# cpx-wroom32d.net
KiCad netlist of a schematic drawn in EAGLE
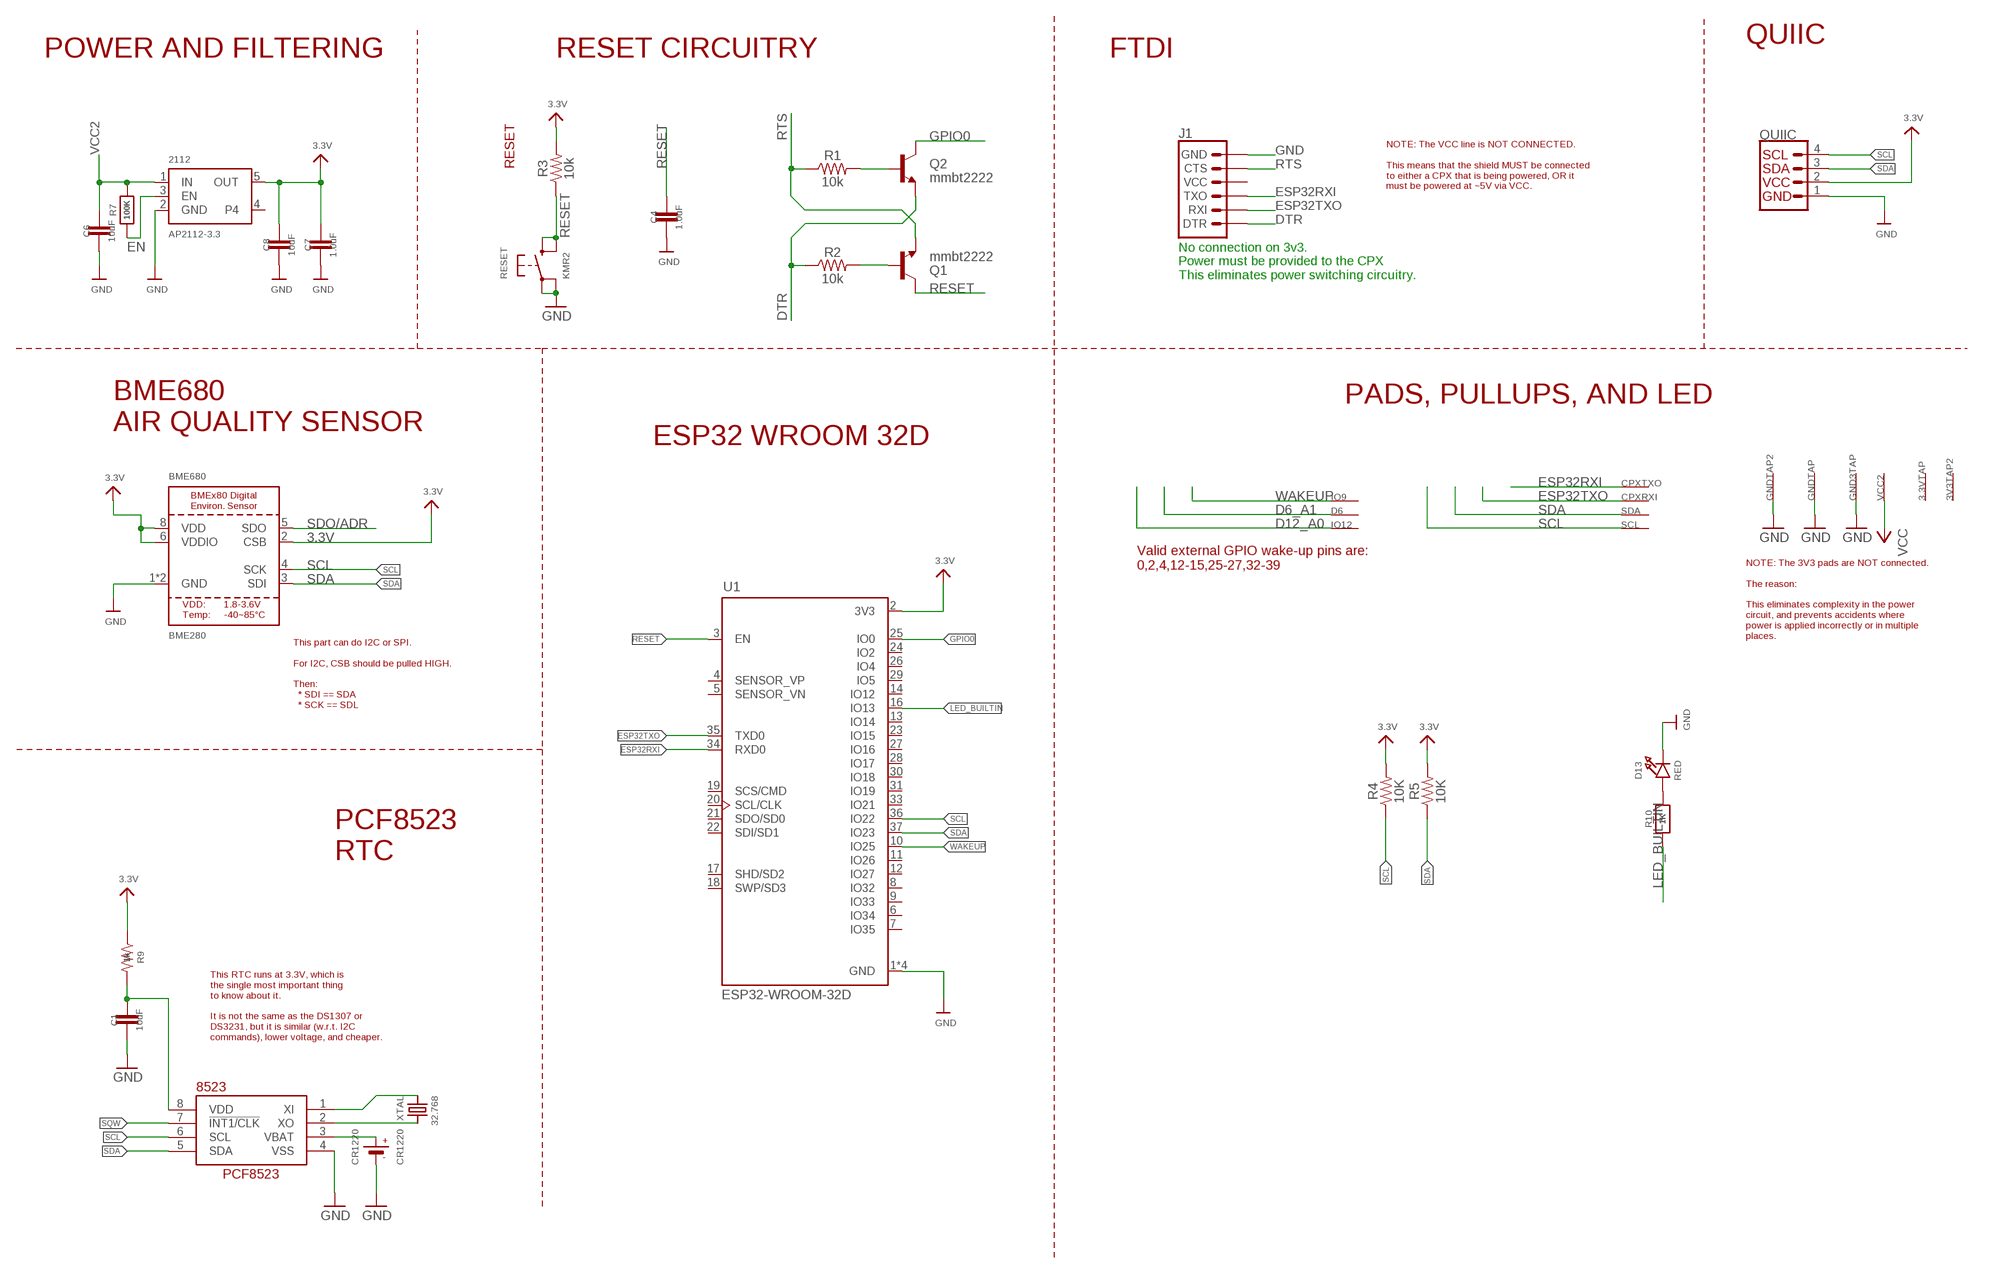
[diagram p0: schematic, sheet 1]

(export (version "E")
  (design (tool "Eeschema 10.0.6"))
  (components
    (comp (ref "3.3VTAP")
      (value "SEWTAP-ALLIGATOR")
      (footprint "eagle-import:SEWALLI")
      (libsource (lib "eagle-import") (part "SEWTAP-ALLIGATOR"))
    )
    (comp (ref "3V3TAP2")
      (value "SEWTAP-ALLIGATOR")
      (footprint "eagle-import:SEWALLI")
      (libsource (lib "eagle-import") (part "SEWTAP-ALLIGATOR"))
    )
    (comp (ref "2112")
      (value "AP2112-3.3")
      (footprint "eagle-import:SOT23-5")
      (libsource (lib "eagle-import") (part "VREG_SOT23-5"))
    )
    (comp (ref "8523")
      (value "RTC_PCF8523T")
      (footprint "eagle-import:SOIC8_150MIL")
      (libsource (lib "eagle-import") (part "RTC_PCF8523T"))
    )
    (comp (ref "BME680")
      (value "BME280")
      (footprint "eagle-import:BME280")
      (libsource (lib "eagle-import") (part "BME280"))
    )
    (comp (ref "C1")
      (value "10uF")
      (footprint "eagle-import:0603")
      (libsource (lib "eagle-import") (part "10UF-0603-6.3V-20%"))
    )
    (comp (ref "C4")
      (value "1.0uF")
      (footprint "eagle-import:0603")
      (libsource (lib "eagle-import") (part "1.0UF-0603-16V-10%"))
    )
    (comp (ref "C6")
      (value "10uF")
      (footprint "eagle-import:0603")
      (libsource (lib "eagle-import") (part "10UF-0603-6.3V-20%"))
    )
    (comp (ref "C7")
      (value "1.0uF")
      (footprint "eagle-import:0603")
      (libsource (lib "eagle-import") (part "1.0UF-0603-16V-10%"))
    )
    (comp (ref "C8")
      (value "10uF")
      (footprint "eagle-import:0603")
      (libsource (lib "eagle-import") (part "10UF-0603-6.3V-20%"))
    )
    (comp (ref "CPXRXI")
      (value "SEWTAP-ALLIGATOR")
      (footprint "eagle-import:SEWALLI")
      (libsource (lib "eagle-import") (part "SEWTAP-ALLIGATOR"))
    )
    (comp (ref "CPXTXO")
      (value "SEWTAP-ALLIGATOR")
      (footprint "eagle-import:SEWALLI")
      (libsource (lib "eagle-import") (part "SEWTAP-ALLIGATOR"))
    )
    (comp (ref "CR1220")
      (value "CR1220")
      (footprint "eagle-import:CR1220")
      (libsource (lib "eagle-import") (part "BATTERYCR1220_SMT"))
    )
    (comp (ref "D6")
      (value "SEWTAP-ALLIGATOR")
      (footprint "eagle-import:SEWALLI")
      (libsource (lib "eagle-import") (part "SEWTAP-ALLIGATOR"))
    )
    (comp (ref "D13")
      (value "RED")
      (footprint "eagle-import:CHIPLED_0805_NOOUTLINE")
      (libsource (lib "eagle-import") (part "LED0805_NOOUTLINE"))
    )
    (comp (ref "GND3TAP")
      (value "SEWTAP-ALLIGATOR")
      (footprint "eagle-import:SEWALLI")
      (libsource (lib "eagle-import") (part "SEWTAP-ALLIGATOR"))
    )
    (comp (ref "GNDTAP")
      (value "SEWTAP-ALLIGATOR")
      (footprint "eagle-import:SEWALLI")
      (libsource (lib "eagle-import") (part "SEWTAP-ALLIGATOR"))
    )
    (comp (ref "GNDTAP2")
      (value "SEWTAP-ALLIGATOR")
      (footprint "eagle-import:SEWALLI")
      (libsource (lib "eagle-import") (part "SEWTAP-ALLIGATOR"))
    )
    (comp (ref "IO9")
      (value "SEWTAP-ALLIGATOR")
      (footprint "eagle-import:SEWALLI")
      (libsource (lib "eagle-import") (part "SEWTAP-ALLIGATOR"))
    )
    (comp (ref "IO12")
      (value "SEWTAP-ALLIGATOR")
      (footprint "eagle-import:SEWALLI")
      (libsource (lib "eagle-import") (part "SEWTAP-ALLIGATOR"))
    )
    (comp (ref "J1")
      (value "6_PIN_SERIAL_TARGETRA_SMT")
      (footprint "eagle-import:6_PIN_SERIAL_TARGET_SIDE_RA_SMT")
      (libsource (lib "eagle-import") (part "6_PIN_SERIAL_TARGETRA_SMT"))
    )
    (comp (ref "Q1")
      (value "mmbt2222")
      (footprint "eagle-import:SOT23-3")
      (libsource (lib "eagle-import") (part "TRANSISTOR_NPNSOT23-3"))
    )
    (comp (ref "Q2")
      (value "mmbt2222")
      (footprint "eagle-import:SOT23-3")
      (libsource (lib "eagle-import") (part "TRANSISTOR_NPNSOT23-3"))
    )
    (comp (ref "QUIIC")
      (value "QWIIC_CONNECTORJS-1MM")
      (footprint "eagle-import:1X04_1MM_RA")
      (libsource (lib "eagle-import") (part "QWIIC_CONNECTORJS-1MM"))
    )
    (comp (ref "R1")
      (value "10k")
      (footprint "eagle-import:0603")
      (libsource (lib "eagle-import") (part "10KOHM-0603-1/10W-1%"))
    )
    (comp (ref "R2")
      (value "10k")
      (footprint "eagle-import:0603")
      (libsource (lib "eagle-import") (part "10KOHM-0603-1/10W-1%"))
    )
    (comp (ref "R3")
      (value "10k")
      (footprint "eagle-import:0603")
      (libsource (lib "eagle-import") (part "10KOHM-0603-1/10W-1%"))
    )
    (comp (ref "R4")
      (value "10K")
      (footprint "eagle-import:0603")
      (libsource (lib "eagle-import") (part "4.7KOHM-0603-1/10W-1%"))
    )
    (comp (ref "R5")
      (value "10K")
      (footprint "eagle-import:0603")
      (libsource (lib "eagle-import") (part "4.7KOHM-0603-1/10W-1%"))
    )
    (comp (ref "R7")
      (value "100K")
      (footprint "eagle-import:0603-NO")
      (libsource (lib "eagle-import") (part "RESISTOR_0603_NOOUT"))
    )
    (comp (ref "R9")
      (value "1k")
      (footprint "eagle-import:0603")
      (libsource (lib "eagle-import") (part "1KOHM-0603-1/10W-1%"))
    )
    (comp (ref "R10")
      (value "1K")
      (footprint "eagle-import:0603-NO")
      (libsource (lib "eagle-import") (part "RESISTOR_0603_NOOUT"))
    )
    (comp (ref "RESET")
      (value "KMR2")
      (footprint "eagle-import:BTN_KMR2_4.6X2.8")
      (libsource (lib "eagle-import") (part "SWITCH_TACT_SMT4.6X2.8"))
    )
    (comp (ref "SCL")
      (value "SEWTAP-ALLIGATOR")
      (footprint "eagle-import:SEWALLI")
      (libsource (lib "eagle-import") (part "SEWTAP-ALLIGATOR"))
    )
    (comp (ref "SDA")
      (value "SEWTAP-ALLIGATOR")
      (footprint "eagle-import:SEWALLI")
      (libsource (lib "eagle-import") (part "SEWTAP-ALLIGATOR"))
    )
    (comp (ref "U1")
      (value "ESP32-WROOM-32D")
      (footprint "eagle-import:MODULE_ESP32-WROOM-32D")
      (fields (field (name "MF") "Espressif Systems"))
      (libsource (lib "eagle-import") (part "ESP32-WROOM-32D"))
    )
    (comp (ref "VCC2")
      (value "SEWTAP-ALLIGATOR")
      (footprint "eagle-import:SEWALLI")
      (libsource (lib "eagle-import") (part "SEWTAP-ALLIGATOR"))
    )
    (comp (ref "XTAL")
      (value "32.768")
      (footprint "eagle-import:CRYSTAL_8X3.8")
      (libsource (lib "eagle-import") (part "CRYSTAL8.0X3.8"))
    )
  )
  (nets
    (net (code "1") (name "/D6_A1") (class "Default")
      (node (ref "D6") (pin "P$1") (pinfunction "SEW_P$1") (pintype "bidirectional"))
    )
    (net (code "2") (name "/D12_A0") (class "Default")
      (node (ref "IO12") (pin "P$1") (pinfunction "SEW_P$1") (pintype "bidirectional"))
    )
    (net (code "3") (name "/DTR") (class "Default")
      (node (ref "J1") (pin "1") (pinfunction "DTR_1") (pintype "passive"))
      (node (ref "Q2") (pin "2") (pinfunction "E_2") (pintype "passive"))
      (node (ref "R2") (pin "1") (pinfunction "1_1") (pintype "passive"))
    )
    (net (code "4") (name "/EN") (class "Default")
      (node (ref "2112") (pin "3") (pinfunction "EN_3") (pintype "input"))
      (node (ref "R7") (pin "1") (pinfunction "1_1") (pintype "passive"))
    )
    (net (code "5") (name "/RTS") (class "Default")
      (node (ref "J1") (pin "5") (pinfunction "CTS_5") (pintype "passive"))
      (node (ref "Q1") (pin "2") (pinfunction "E_2") (pintype "passive"))
      (node (ref "R1") (pin "1") (pinfunction "1_1") (pintype "passive"))
    )
    (net (code "6") (name "/SDO{slash}ADR") (class "Default")
      (node (ref "BME680") (pin "5") (pinfunction "SDO_5") (pintype "output"))
    )
    (net (code "7") (name "/VCC2") (class "Default")
      (node (ref "2112") (pin "1") (pinfunction "IN_1") (pintype "power_in"))
      (node (ref "C6") (pin "1") (pinfunction "1_1") (pintype "passive"))
      (node (ref "R7") (pin "2") (pinfunction "2_2") (pintype "passive"))
    )
    (net (code "8") (name "3.3V") (class "Default")
      (node (ref "2112") (pin "5") (pinfunction "OUT_5") (pintype "power_in"))
      (node (ref "BME680") (pin "2") (pinfunction "CSB_2") (pintype "input"))
      (node (ref "BME680") (pin "6") (pinfunction "VDDIO_6") (pintype "power_in"))
      (node (ref "BME680") (pin "8") (pinfunction "VDD_8") (pintype "power_in"))
      (node (ref "C7") (pin "1") (pinfunction "1_1") (pintype "passive"))
      (node (ref "C8") (pin "1") (pinfunction "1_1") (pintype "passive"))
      (node (ref "QUIIC") (pin "2") (pinfunction "VCC_2") (pintype "power_in"))
      (node (ref "R3") (pin "2") (pinfunction "2_2") (pintype "passive"))
      (node (ref "R4") (pin "2") (pinfunction "2_2") (pintype "passive"))
      (node (ref "R5") (pin "2") (pinfunction "2_2") (pintype "passive"))
      (node (ref "R9") (pin "1") (pinfunction "1_1") (pintype "passive"))
      (node (ref "U1") (pin "2") (pinfunction "3V3_2") (pintype "power_in"))
    )
    (net (code "9") (name "ESP32RXI") (class "Default")
      (node (ref "CPXTXO") (pin "P$1") (pinfunction "SEW_P$1") (pintype "bidirectional"))
      (node (ref "J1") (pin "2") (pinfunction "TXO_2") (pintype "passive"))
      (node (ref "U1") (pin "34") (pinfunction "RXD0_34") (pintype "bidirectional"))
    )
    (net (code "10") (name "ESP32TXO") (class "Default")
      (node (ref "CPXRXI") (pin "P$1") (pinfunction "SEW_P$1") (pintype "bidirectional"))
      (node (ref "J1") (pin "3") (pinfunction "RXI_3") (pintype "passive"))
      (node (ref "U1") (pin "35") (pinfunction "TXD0_35") (pintype "bidirectional"))
    )
    (net (code "11") (name "GND") (class "Default")
      (node (ref "2112") (pin "2") (pinfunction "GND_2") (pintype "power_in"))
      (node (ref "8523") (pin "4") (pinfunction "VSS_4") (pintype "power_in"))
      (node (ref "BME680") (pin "1") (pinfunction "GND_1") (pintype "power_in"))
      (node (ref "BME680") (pin "7") (pinfunction "GND_7") (pintype "power_in"))
      (node (ref "C1") (pin "2") (pinfunction "2_2") (pintype "passive"))
      (node (ref "C4") (pin "2") (pinfunction "2_2") (pintype "passive"))
      (node (ref "C6") (pin "2") (pinfunction "2_2") (pintype "passive"))
      (node (ref "C7") (pin "2") (pinfunction "2_2") (pintype "passive"))
      (node (ref "C8") (pin "2") (pinfunction "2_2") (pintype "passive"))
      (node (ref "CR1220") (pin "-") (pinfunction "-_-") (pintype "passive"))
      (node (ref "D13") (pin "C") (pinfunction "C_C") (pintype "passive"))
      (node (ref "GND3TAP") (pin "P$1") (pinfunction "SEW_P$1") (pintype "bidirectional"))
      (node (ref "GNDTAP") (pin "P$1") (pinfunction "SEW_P$1") (pintype "bidirectional"))
      (node (ref "GNDTAP2") (pin "P$1") (pinfunction "SEW_P$1") (pintype "bidirectional"))
      (node (ref "J1") (pin "6") (pinfunction "GND_6") (pintype "passive"))
      (node (ref "QUIIC") (pin "1") (pinfunction "GND_1") (pintype "power_in"))
      (node (ref "RESET") (pin "A") (pinfunction "P_A") (pintype "passive"))
      (node (ref "RESET") (pin "A'") (pinfunction "P1_A'") (pintype "passive"))
      (node (ref "U1") (pin "1") (pinfunction "GND_1") (pintype "power_in"))
      (node (ref "U1") (pin "15") (pinfunction "GND_15") (pintype "power_in"))
      (node (ref "U1") (pin "38") (pinfunction "GND_38") (pintype "power_in"))
      (node (ref "U1") (pin "39") (pinfunction "GND_39") (pintype "power_in"))
    )
    (net (code "12") (name "GPIO0") (class "Default")
      (node (ref "Q2") (pin "3") (pinfunction "C_3") (pintype "passive"))
      (node (ref "U1") (pin "25") (pinfunction "IO0_25") (pintype "bidirectional"))
    )
    (net (code "13") (name "LED_BUILTIN") (class "Default")
      (node (ref "R10") (pin "1") (pinfunction "1_1") (pintype "passive"))
      (node (ref "U1") (pin "16") (pinfunction "IO13_16") (pintype "bidirectional"))
    )
    (net (code "14") (name "Net-(8523-VBAT)") (class "Default")
      (node (ref "8523") (pin "3") (pinfunction "VBAT_3") (pintype "power_in"))
      (node (ref "CR1220") (pin "+$1") (pinfunction "+_+$1") (pintype "passive"))
    )
    (net (code "15") (name "Net-(8523-VDD)") (class "Default")
      (node (ref "8523") (pin "8") (pinfunction "VDD_8") (pintype "power_in"))
      (node (ref "C1") (pin "1") (pinfunction "1_1") (pintype "passive"))
      (node (ref "R9") (pin "2") (pinfunction "2_2") (pintype "passive"))
    )
    (net (code "16") (name "Net-(8523-XI)") (class "Default")
      (node (ref "8523") (pin "1") (pinfunction "XI_1") (pintype "input"))
      (node (ref "XTAL") (pin "P$1") (pinfunction "1_P$1") (pintype "passive"))
    )
    (net (code "17") (name "Net-(8523-XO)") (class "Default")
      (node (ref "8523") (pin "2") (pinfunction "XO_2") (pintype "output"))
      (node (ref "XTAL") (pin "P$4") (pinfunction "2_P$4") (pintype "passive"))
    )
    (net (code "18") (name "Net-(D13-PadA)") (class "Default")
      (node (ref "D13") (pin "A") (pinfunction "A_A") (pintype "passive"))
      (node (ref "R10") (pin "2") (pinfunction "2_2") (pintype "passive"))
    )
    (net (code "19") (name "Net-(Q1-B)") (class "Default")
      (node (ref "Q1") (pin "1") (pinfunction "B_1") (pintype "passive"))
      (node (ref "R2") (pin "2") (pinfunction "2_2") (pintype "passive"))
    )
    (net (code "20") (name "Net-(Q2-B)") (class "Default")
      (node (ref "Q2") (pin "1") (pinfunction "B_1") (pintype "passive"))
      (node (ref "R1") (pin "2") (pinfunction "2_2") (pintype "passive"))
    )
    (net (code "21") (name "RESET") (class "Default")
      (node (ref "C4") (pin "1") (pinfunction "1_1") (pintype "passive"))
      (node (ref "Q1") (pin "3") (pinfunction "C_3") (pintype "passive"))
      (node (ref "R3") (pin "1") (pinfunction "1_1") (pintype "passive"))
      (node (ref "RESET") (pin "B") (pinfunction "S_B") (pintype "passive"))
      (node (ref "RESET") (pin "B'") (pinfunction "S1_B'") (pintype "passive"))
      (node (ref "U1") (pin "3") (pinfunction "EN_3") (pintype "input"))
    )
    (net (code "22") (name "SCL") (class "Default")
      (node (ref "8523") (pin "6") (pinfunction "SCL_6") (pintype "bidirectional"))
      (node (ref "BME680") (pin "4") (pinfunction "SCK_4") (pintype "input"))
      (node (ref "QUIIC") (pin "4") (pinfunction "SCL_4") (pintype "passive"))
      (node (ref "R4") (pin "1") (pinfunction "1_1") (pintype "passive"))
      (node (ref "SCL") (pin "P$1") (pinfunction "SEW_P$1") (pintype "bidirectional"))
      (node (ref "U1") (pin "36") (pinfunction "IO22_36") (pintype "bidirectional"))
    )
    (net (code "23") (name "SDA") (class "Default")
      (node (ref "8523") (pin "5") (pinfunction "SDA_5") (pintype "bidirectional"))
      (node (ref "BME680") (pin "3") (pinfunction "SDI_3") (pintype "input"))
      (node (ref "QUIIC") (pin "3") (pinfunction "SDA_3") (pintype "passive"))
      (node (ref "R5") (pin "1") (pinfunction "1_1") (pintype "passive"))
      (node (ref "SDA") (pin "P$1") (pinfunction "SEW_P$1") (pintype "bidirectional"))
      (node (ref "U1") (pin "37") (pinfunction "IO23_37") (pintype "bidirectional"))
    )
    (net (code "24") (name "SQW") (class "Default")
      (node (ref "8523") (pin "7") (pinfunction "~{INT1/CLK}_7") (pintype "output"))
    )
    (net (code "25") (name "VCC") (class "Default")
      (node (ref "VCC2") (pin "P$1") (pinfunction "SEW_P$1") (pintype "bidirectional"))
    )
    (net (code "26") (name "WAKEUP") (class "Default")
      (node (ref "IO9") (pin "P$1") (pinfunction "SEW_P$1") (pintype "bidirectional"))
      (node (ref "U1") (pin "10") (pinfunction "IO25_10") (pintype "bidirectional"))
    )
    (net (code "27") (name "unconnected-(3.3VTAP-SEW-PadP$1)") (class "Default")
      (node (ref "3.3VTAP") (pin "P$1") (pinfunction "SEW_P$1") (pintype "bidirectional"))
    )
    (net (code "28") (name "unconnected-(3V3TAP2-SEW-PadP$1)") (class "Default")
      (node (ref "3V3TAP2") (pin "P$1") (pinfunction "SEW_P$1") (pintype "bidirectional"))
    )
    (net (code "29") (name "unconnected-(2112-P4-Pad4)") (class "Default")
      (node (ref "2112") (pin "4") (pinfunction "P4_4") (pintype "bidirectional"))
    )
    (net (code "30") (name "unconnected-(J1-VCC-Pad4)") (class "Default")
      (node (ref "J1") (pin "4") (pinfunction "VCC_4") (pintype "passive"))
    )
    (net (code "31") (name "unconnected-(U1-IO2-Pad24)") (class "Default")
      (node (ref "U1") (pin "24") (pinfunction "IO2_24") (pintype "bidirectional"))
    )
    (net (code "32") (name "unconnected-(U1-IO4-Pad26)") (class "Default")
      (node (ref "U1") (pin "26") (pinfunction "IO4_26") (pintype "bidirectional"))
    )
    (net (code "33") (name "unconnected-(U1-IO5-Pad29)") (class "Default")
      (node (ref "U1") (pin "29") (pinfunction "IO5_29") (pintype "bidirectional"))
    )
    (net (code "34") (name "unconnected-(U1-IO12-Pad14)") (class "Default")
      (node (ref "U1") (pin "14") (pinfunction "IO12_14") (pintype "bidirectional"))
    )
    (net (code "35") (name "unconnected-(U1-IO14-Pad13)") (class "Default")
      (node (ref "U1") (pin "13") (pinfunction "IO14_13") (pintype "bidirectional"))
    )
    (net (code "36") (name "unconnected-(U1-IO15-Pad23)") (class "Default")
      (node (ref "U1") (pin "23") (pinfunction "IO15_23") (pintype "bidirectional"))
    )
    (net (code "37") (name "unconnected-(U1-IO16-Pad27)") (class "Default")
      (node (ref "U1") (pin "27") (pinfunction "IO16_27") (pintype "bidirectional"))
    )
    (net (code "38") (name "unconnected-(U1-IO17-Pad28)") (class "Default")
      (node (ref "U1") (pin "28") (pinfunction "IO17_28") (pintype "bidirectional"))
    )
    (net (code "39") (name "unconnected-(U1-IO18-Pad30)") (class "Default")
      (node (ref "U1") (pin "30") (pinfunction "IO18_30") (pintype "bidirectional"))
    )
    (net (code "40") (name "unconnected-(U1-IO19-Pad31)") (class "Default")
      (node (ref "U1") (pin "31") (pinfunction "IO19_31") (pintype "bidirectional"))
    )
    (net (code "41") (name "unconnected-(U1-IO21-Pad33)") (class "Default")
      (node (ref "U1") (pin "33") (pinfunction "IO21_33") (pintype "bidirectional"))
    )
    (net (code "42") (name "unconnected-(U1-IO26-Pad11)") (class "Default")
      (node (ref "U1") (pin "11") (pinfunction "IO26_11") (pintype "bidirectional"))
    )
    (net (code "43") (name "unconnected-(U1-IO27-Pad12)") (class "Default")
      (node (ref "U1") (pin "12") (pinfunction "IO27_12") (pintype "bidirectional"))
    )
    (net (code "44") (name "unconnected-(U1-IO32-Pad8)") (class "Default")
      (node (ref "U1") (pin "8") (pinfunction "IO32_8") (pintype "bidirectional"))
    )
    (net (code "45") (name "unconnected-(U1-IO33-Pad9)") (class "Default")
      (node (ref "U1") (pin "9") (pinfunction "IO33_9") (pintype "bidirectional"))
    )
    (net (code "46") (name "unconnected-(U1-IO34-Pad6)") (class "Default")
      (node (ref "U1") (pin "6") (pinfunction "IO34_6") (pintype "bidirectional"))
    )
    (net (code "47") (name "unconnected-(U1-IO35-Pad7)") (class "Default")
      (node (ref "U1") (pin "7") (pinfunction "IO35_7") (pintype "bidirectional"))
    )
    (net (code "48") (name "unconnected-(U1-SCL{slash}CLK-Pad20)") (class "Default")
      (node (ref "U1") (pin "20") (pinfunction "SCL/CLK_20") (pintype "bidirectional"))
    )
    (net (code "49") (name "unconnected-(U1-SCS{slash}CMD-Pad19)") (class "Default")
      (node (ref "U1") (pin "19") (pinfunction "SCS/CMD_19") (pintype "bidirectional"))
    )
    (net (code "50") (name "unconnected-(U1-SDI{slash}SD1-Pad22)") (class "Default")
      (node (ref "U1") (pin "22") (pinfunction "SDI/SD1_22") (pintype "bidirectional"))
    )
    (net (code "51") (name "unconnected-(U1-SDO{slash}SD0-Pad21)") (class "Default")
      (node (ref "U1") (pin "21") (pinfunction "SDO/SD0_21") (pintype "bidirectional"))
    )
    (net (code "52") (name "unconnected-(U1-SENSOR_VN-Pad5)") (class "Default")
      (node (ref "U1") (pin "5") (pinfunction "SENSOR_VN_5") (pintype "input"))
    )
    (net (code "53") (name "unconnected-(U1-SENSOR_VP-Pad4)") (class "Default")
      (node (ref "U1") (pin "4") (pinfunction "SENSOR_VP_4") (pintype "input"))
    )
    (net (code "54") (name "unconnected-(U1-SHD{slash}SD2-Pad17)") (class "Default")
      (node (ref "U1") (pin "17") (pinfunction "SHD/SD2_17") (pintype "bidirectional"))
    )
    (net (code "55") (name "unconnected-(U1-SWP{slash}SD3-Pad18)") (class "Default")
      (node (ref "U1") (pin "18") (pinfunction "SWP/SD3_18") (pintype "bidirectional"))
    )
  )
)
